# Sheet1-driver.net
KiCad netlist of a schematic drawn in Altium Designer
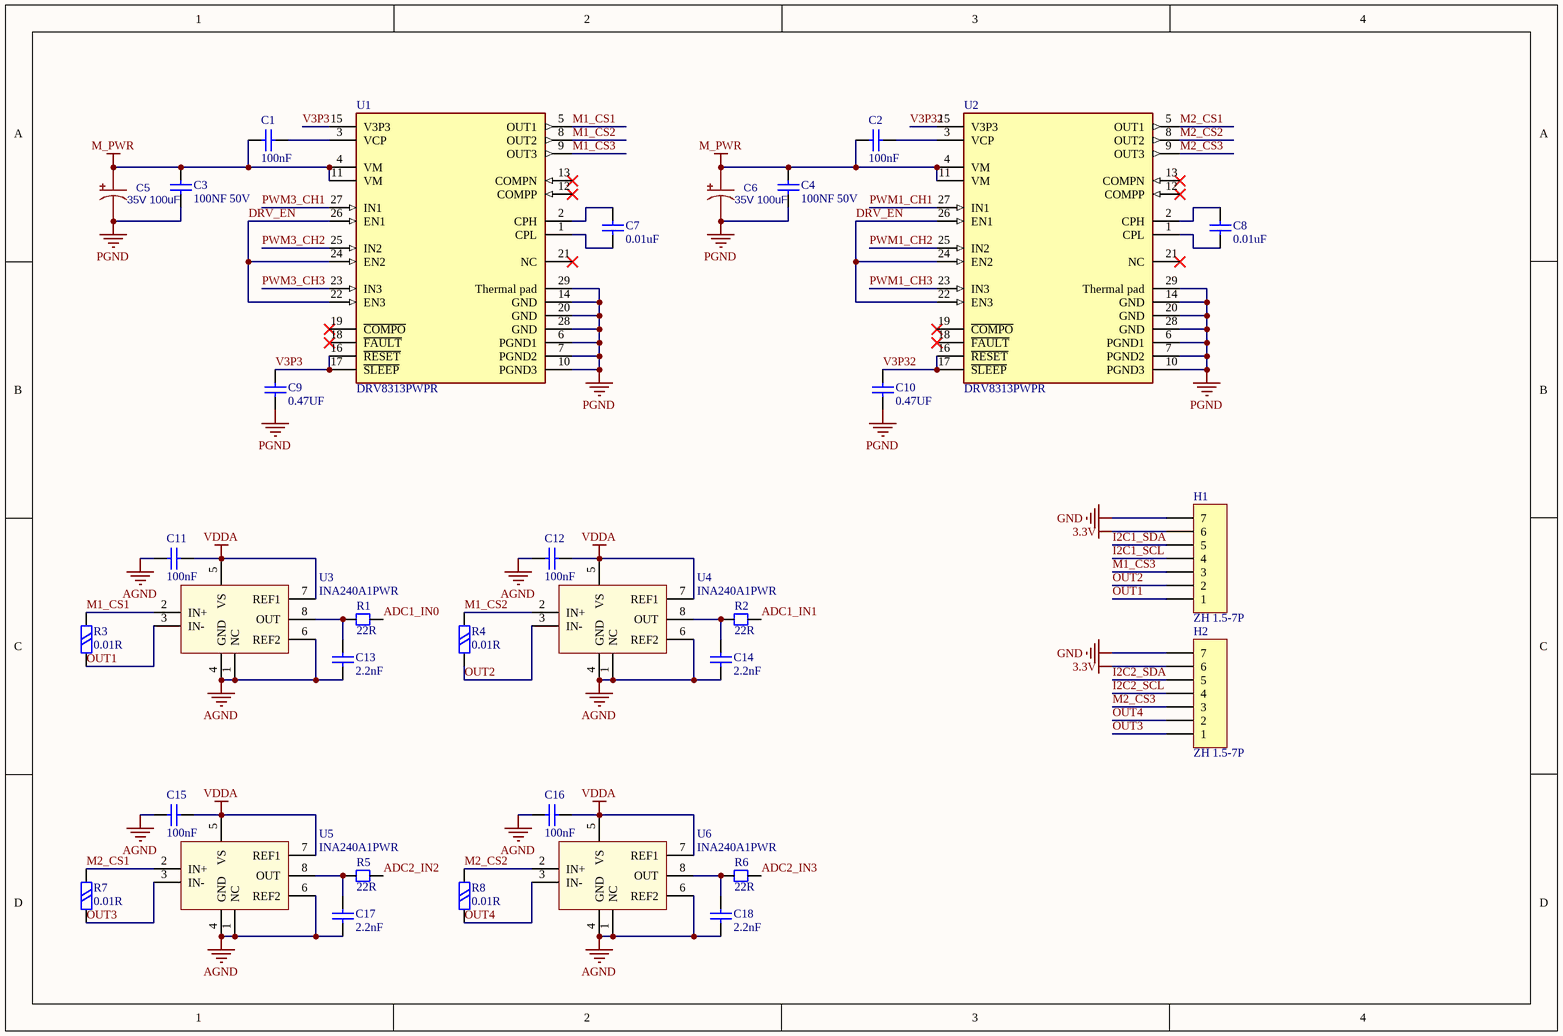
[diagram p0: Sheet1-driver.SchDoc]

(export (version "E")
  (design (tool "Eeschema 10.0.6"))
  (components
    (comp (ref "C1")
      (value "100nF")
      (footprint "CC1608-0603")
      (description "0603封装的电容")
      (fields (field (name "PUBLISHER") "Altium Limited"))
      (libsource (lib "base") (part "Cap Chip 0603"))
    )
    (comp (ref "C2")
      (value "100nF")
      (footprint "CC1608-0603")
      (description "0603封装的电容")
      (fields (field (name "PUBLISHER") "Altium Limited"))
      (libsource (lib "base") (part "Cap Chip 0603"))
    )
    (comp (ref "C3")
      (value "100NF 50V")
      (footprint "CC1608-0603")
      (description "0603封装的电容")
      (fields (field (name "PUBLISHER") "Altium Limited"))
      (libsource (lib "base") (part "Cap Chip 0603"))
    )
    (comp (ref "C4")
      (value "100NF 50V")
      (footprint "CC1608-0603")
      (description "0603封装的电容")
      (fields (field (name "PUBLISHER") "Altium Limited"))
      (libsource (lib "base") (part "Cap Chip 0603"))
    )
    (comp (ref "C5")
      (value "35V 100uF")
      (footprint "CAP-SMD_D6.3")
      (description "铝点解电容")
      (fields
        (field (name "BOM_SUPPLIER PART") "C413527")
        (field (name "BOM_MANUFACTURER PART") "EEEFP1C681AP")
        (field (name "CONTRIBUTOR") "LCSC")
      )
      (libsource (lib "base") (part "Cap ECAP SMD"))
    )
    (comp (ref "C6")
      (value "35V 100uF")
      (footprint "CAP-SMD_D6.3")
      (description "铝点解电容")
      (fields
        (field (name "BOM_SUPPLIER PART") "C413527")
        (field (name "BOM_MANUFACTURER PART") "EEEFP1C681AP")
        (field (name "CONTRIBUTOR") "LCSC")
      )
      (libsource (lib "base") (part "Cap ECAP SMD"))
    )
    (comp (ref "C7")
      (value "0.01uF")
      (footprint "CC1608-0603")
      (description "0603封装的电容")
      (fields (field (name "PUBLISHER") "Altium Limited"))
      (libsource (lib "base") (part "Cap Chip 0603"))
    )
    (comp (ref "C8")
      (value "0.01uF")
      (footprint "CC1608-0603")
      (description "0603封装的电容")
      (fields (field (name "PUBLISHER") "Altium Limited"))
      (libsource (lib "base") (part "Cap Chip 0603"))
    )
    (comp (ref "C9")
      (value "0.47UF")
      (footprint "CC1608-0603")
      (description "0603封装的电容")
      (fields (field (name "PUBLISHER") "Altium Limited"))
      (libsource (lib "base") (part "Cap Chip 0603"))
    )
    (comp (ref "C10")
      (value "0.47UF")
      (footprint "CC1608-0603")
      (description "0603封装的电容")
      (fields (field (name "PUBLISHER") "Altium Limited"))
      (libsource (lib "base") (part "Cap Chip 0603"))
    )
    (comp (ref "C11")
      (value "100nF")
      (footprint "CC1608-0603")
      (description "0603封装的电容")
      (fields (field (name "PUBLISHER") "Altium Limited"))
      (libsource (lib "base") (part "Cap Chip 0603"))
    )
    (comp (ref "C12")
      (value "100nF")
      (footprint "CC1608-0603")
      (description "0603封装的电容")
      (fields (field (name "PUBLISHER") "Altium Limited"))
      (libsource (lib "base") (part "Cap Chip 0603"))
    )
    (comp (ref "C13")
      (value "2.2nF")
      (footprint "CC1608-0603")
      (description "0603封装的电容")
      (fields (field (name "PUBLISHER") "Altium Limited"))
      (libsource (lib "base") (part "Cap Chip 0603"))
    )
    (comp (ref "C14")
      (value "2.2nF")
      (footprint "CC1608-0603")
      (description "0603封装的电容")
      (fields (field (name "PUBLISHER") "Altium Limited"))
      (libsource (lib "base") (part "Cap Chip 0603"))
    )
    (comp (ref "C15")
      (value "100nF")
      (footprint "CC1608-0603")
      (description "0603封装的电容")
      (fields (field (name "PUBLISHER") "Altium Limited"))
      (libsource (lib "base") (part "Cap Chip 0603"))
    )
    (comp (ref "C16")
      (value "100nF")
      (footprint "CC1608-0603")
      (description "0603封装的电容")
      (fields (field (name "PUBLISHER") "Altium Limited"))
      (libsource (lib "base") (part "Cap Chip 0603"))
    )
    (comp (ref "C17")
      (value "2.2nF")
      (footprint "CC1608-0603")
      (description "0603封装的电容")
      (fields (field (name "PUBLISHER") "Altium Limited"))
      (libsource (lib "base") (part "Cap Chip 0603"))
    )
    (comp (ref "C18")
      (value "2.2nF")
      (footprint "CC1608-0603")
      (description "0603封装的电容")
      (fields (field (name "PUBLISHER") "Altium Limited"))
      (libsource (lib "base") (part "Cap Chip 0603"))
    )
    (comp (ref "H1")
      (value "ZH 1.5-7P")
      (footprint "ZH1.5-7P")
      (description "ZH1.5-7P 间距1.5的贴片连接座")
      (libsource (lib "Connectors") (part "ZH 1.5-7P"))
    )
    (comp (ref "H2")
      (value "ZH 1.5-7P")
      (footprint "ZH1.5-7P")
      (description "ZH1.5-7P 间距1.5的贴片连接座")
      (libsource (lib "Connectors") (part "ZH 1.5-7P"))
    )
    (comp (ref "R1")
      (value "22R")
      (footprint "CR1608-0603")
      (description "0603封装电阻")
      (fields (field (name "PUBLISHER") "Altium Limited"))
      (libsource (lib "base") (part "Resistor Chip 0603"))
    )
    (comp (ref "R2")
      (value "22R")
      (footprint "CR1608-0603")
      (description "0603封装电阻")
      (fields (field (name "PUBLISHER") "Altium Limited"))
      (libsource (lib "base") (part "Resistor Chip 0603"))
    )
    (comp (ref "R3")
      (value "0.01R")
      (footprint "CR3216-1206")
      (description "1206封装电阻")
      (fields (field (name "PUBLISHER") "Altium Limited"))
      (libsource (lib "base") (part "Resistor Chip 1206"))
    )
    (comp (ref "R4")
      (value "0.01R")
      (footprint "CR3216-1206")
      (description "1206封装电阻")
      (fields (field (name "PUBLISHER") "Altium Limited"))
      (libsource (lib "base") (part "Resistor Chip 1206"))
    )
    (comp (ref "R5")
      (value "22R")
      (footprint "CR1608-0603")
      (description "0603封装电阻")
      (fields (field (name "PUBLISHER") "Altium Limited"))
      (libsource (lib "base") (part "Resistor Chip 0603"))
    )
    (comp (ref "R6")
      (value "22R")
      (footprint "CR1608-0603")
      (description "0603封装电阻")
      (fields (field (name "PUBLISHER") "Altium Limited"))
      (libsource (lib "base") (part "Resistor Chip 0603"))
    )
    (comp (ref "R7")
      (value "0.01R")
      (footprint "CR3216-1206")
      (description "1206封装电阻")
      (fields (field (name "PUBLISHER") "Altium Limited"))
      (libsource (lib "base") (part "Resistor Chip 1206"))
    )
    (comp (ref "R8")
      (value "0.01R")
      (footprint "CR3216-1206")
      (description "1206封装电阻")
      (fields (field (name "PUBLISHER") "Altium Limited"))
      (libsource (lib "base") (part "Resistor Chip 1206"))
    )
    (comp (ref "U1")
      (value "DRV8313PWPR")
      (footprint "HTSSOP-28")
      (description "独立控制的半 H 桥驱动器,主要用于驱动一个三项无刷电机IC MOTOR DRIVER 8V-60V 28HTSSOP")
      (libsource (lib "PB-Chip") (part "DRV8313"))
    )
    (comp (ref "U2")
      (value "DRV8313PWPR")
      (footprint "HTSSOP-28")
      (description "独立控制的半 H 桥驱动器,主要用于驱动一个三项无刷电机IC MOTOR DRIVER 8V-60V 28HTSSOP")
      (libsource (lib "PB-Chip") (part "DRV8313"))
    )
    (comp (ref "U3")
      (value "INA240A1PWR")
      (footprint "TSSOP-8")
      (description "超精密电流检测放大器")
      (libsource (lib "power-chip") (part "INA240A1PWR"))
    )
    (comp (ref "U4")
      (value "INA240A1PWR")
      (footprint "TSSOP-8")
      (description "超精密电流检测放大器")
      (libsource (lib "power-chip") (part "INA240A1PWR"))
    )
    (comp (ref "U5")
      (value "INA240A1PWR")
      (footprint "TSSOP-8")
      (description "超精密电流检测放大器")
      (libsource (lib "power-chip") (part "INA240A1PWR"))
    )
    (comp (ref "U6")
      (value "INA240A1PWR")
      (footprint "TSSOP-8")
      (description "超精密电流检测放大器")
      (libsource (lib "power-chip") (part "INA240A1PWR"))
    )
  )
  (nets
    (net (code "1") (name "/ADC1_IN0") (class "Default")
      (node (ref "R1") (pin "1") (pinfunction "1_1") (pintype "passive"))
    )
    (net (code "2") (name "/ADC1_IN1") (class "Default")
      (node (ref "R2") (pin "1") (pinfunction "1_1") (pintype "passive"))
    )
    (net (code "3") (name "/ADC2_IN2") (class "Default")
      (node (ref "R5") (pin "1") (pinfunction "1_1") (pintype "passive"))
    )
    (net (code "4") (name "/ADC2_IN3") (class "Default")
      (node (ref "R6") (pin "1") (pinfunction "1_1") (pintype "passive"))
    )
    (net (code "5") (name "/DRV_EN") (class "Default")
      (node (ref "U1") (pin "22") (pinfunction "EN3_22") (pintype "input"))
      (node (ref "U1") (pin "24") (pinfunction "EN2_24") (pintype "input"))
      (node (ref "U1") (pin "26") (pinfunction "EN1_26") (pintype "input"))
      (node (ref "U2") (pin "22") (pinfunction "EN3_22") (pintype "input"))
      (node (ref "U2") (pin "24") (pinfunction "EN2_24") (pintype "input"))
      (node (ref "U2") (pin "26") (pinfunction "EN1_26") (pintype "input"))
    )
    (net (code "6") (name "/I2C1_SCL") (class "Default")
      (node (ref "H1") (pin "4") (pinfunction "4_4") (pintype "passive"))
    )
    (net (code "7") (name "/I2C1_SDA") (class "Default")
      (node (ref "H1") (pin "5") (pinfunction "5_5") (pintype "passive"))
    )
    (net (code "8") (name "/I2C2_SCL") (class "Default")
      (node (ref "H2") (pin "4") (pinfunction "4_4") (pintype "passive"))
    )
    (net (code "9") (name "/I2C2_SDA") (class "Default")
      (node (ref "H2") (pin "5") (pinfunction "5_5") (pintype "passive"))
    )
    (net (code "10") (name "/M1_CS1") (class "Default")
      (node (ref "R3") (pin "2") (pinfunction "2_2") (pintype "passive"))
      (node (ref "U1") (pin "5") (pinfunction "OUT1_5") (pintype "output"))
      (node (ref "U3") (pin "2") (pinfunction "IN+_2") (pintype "passive"))
    )
    (net (code "11") (name "/M1_CS2") (class "Default")
      (node (ref "R4") (pin "2") (pinfunction "2_2") (pintype "passive"))
      (node (ref "U1") (pin "8") (pinfunction "OUT2_8") (pintype "output"))
      (node (ref "U4") (pin "2") (pinfunction "IN+_2") (pintype "passive"))
    )
    (net (code "12") (name "/M1_CS3") (class "Default")
      (node (ref "H1") (pin "3") (pinfunction "3_3") (pintype "passive"))
      (node (ref "U1") (pin "9") (pinfunction "OUT3_9") (pintype "output"))
    )
    (net (code "13") (name "/M2_CS1") (class "Default")
      (node (ref "R7") (pin "2") (pinfunction "2_2") (pintype "passive"))
      (node (ref "U2") (pin "5") (pinfunction "OUT1_5") (pintype "output"))
      (node (ref "U5") (pin "2") (pinfunction "IN+_2") (pintype "passive"))
    )
    (net (code "14") (name "/M2_CS2") (class "Default")
      (node (ref "R8") (pin "2") (pinfunction "2_2") (pintype "passive"))
      (node (ref "U2") (pin "8") (pinfunction "OUT2_8") (pintype "output"))
      (node (ref "U6") (pin "2") (pinfunction "IN+_2") (pintype "passive"))
    )
    (net (code "15") (name "/M2_CS3") (class "Default")
      (node (ref "H2") (pin "3") (pinfunction "3_3") (pintype "passive"))
      (node (ref "U2") (pin "9") (pinfunction "OUT3_9") (pintype "output"))
    )
    (net (code "16") (name "/OUT1") (class "Default")
      (node (ref "H1") (pin "1") (pinfunction "1_1") (pintype "passive"))
      (node (ref "R3") (pin "1") (pinfunction "1_1") (pintype "passive"))
      (node (ref "U3") (pin "3") (pinfunction "IN-_3") (pintype "passive"))
    )
    (net (code "17") (name "/OUT2") (class "Default")
      (node (ref "H1") (pin "2") (pinfunction "2_2") (pintype "passive"))
      (node (ref "R4") (pin "1") (pinfunction "1_1") (pintype "passive"))
      (node (ref "U4") (pin "3") (pinfunction "IN-_3") (pintype "passive"))
    )
    (net (code "18") (name "/OUT3") (class "Default")
      (node (ref "H2") (pin "1") (pinfunction "1_1") (pintype "passive"))
      (node (ref "R7") (pin "1") (pinfunction "1_1") (pintype "passive"))
      (node (ref "U5") (pin "3") (pinfunction "IN-_3") (pintype "passive"))
    )
    (net (code "19") (name "/OUT4") (class "Default")
      (node (ref "H2") (pin "2") (pinfunction "2_2") (pintype "passive"))
      (node (ref "R8") (pin "1") (pinfunction "1_1") (pintype "passive"))
      (node (ref "U6") (pin "3") (pinfunction "IN-_3") (pintype "passive"))
    )
    (net (code "20") (name "/PWM1_CH1") (class "Default")
      (node (ref "U2") (pin "27") (pinfunction "IN1_27") (pintype "input"))
    )
    (net (code "21") (name "/PWM1_CH2") (class "Default")
      (node (ref "U2") (pin "25") (pinfunction "IN2_25") (pintype "input"))
    )
    (net (code "22") (name "/PWM1_CH3") (class "Default")
      (node (ref "U2") (pin "23") (pinfunction "IN3_23") (pintype "input"))
    )
    (net (code "23") (name "/PWM3_CH1") (class "Default")
      (node (ref "U1") (pin "27") (pinfunction "IN1_27") (pintype "input"))
    )
    (net (code "24") (name "/PWM3_CH2") (class "Default")
      (node (ref "U1") (pin "25") (pinfunction "IN2_25") (pintype "input"))
    )
    (net (code "25") (name "/PWM3_CH3") (class "Default")
      (node (ref "U1") (pin "23") (pinfunction "IN3_23") (pintype "input"))
    )
    (net (code "26") (name "/V3P3") (class "Default")
      (node (ref "C9") (pin "1") (pinfunction "1_1") (pintype "passive"))
      (node (ref "U1") (pin "15") (pinfunction "V3P3_15") (pintype "power_in"))
      (node (ref "U1") (pin "16") (pinfunction "~{RESET}_16") (pintype "passive"))
      (node (ref "U1") (pin "17") (pinfunction "~{SLEEP}_17") (pintype "passive"))
    )
    (net (code "27") (name "/V3P32") (class "Default")
      (node (ref "C10") (pin "1") (pinfunction "1_1") (pintype "passive"))
      (node (ref "U2") (pin "15") (pinfunction "V3P3_15") (pintype "power_in"))
      (node (ref "U2") (pin "16") (pinfunction "~{RESET}_16") (pintype "passive"))
      (node (ref "U2") (pin "17") (pinfunction "~{SLEEP}_17") (pintype "passive"))
    )
    (net (code "28") (name "3.3V") (class "Default")
      (node (ref "H1") (pin "6") (pinfunction "6_6") (pintype "passive"))
      (node (ref "H2") (pin "6") (pinfunction "6_6") (pintype "passive"))
    )
    (net (code "29") (name "AGND") (class "Default")
      (node (ref "C11") (pin "2") (pinfunction "2_2") (pintype "passive"))
      (node (ref "C12") (pin "2") (pinfunction "2_2") (pintype "passive"))
      (node (ref "C13") (pin "1") (pinfunction "1_1") (pintype "passive"))
      (node (ref "C14") (pin "1") (pinfunction "1_1") (pintype "passive"))
      (node (ref "C15") (pin "2") (pinfunction "2_2") (pintype "passive"))
      (node (ref "C16") (pin "2") (pinfunction "2_2") (pintype "passive"))
      (node (ref "C17") (pin "1") (pinfunction "1_1") (pintype "passive"))
      (node (ref "C18") (pin "1") (pinfunction "1_1") (pintype "passive"))
      (node (ref "U3") (pin "1") (pinfunction "NC_1") (pintype "passive"))
      (node (ref "U3") (pin "4") (pinfunction "GND_4") (pintype "passive"))
      (node (ref "U3") (pin "6") (pinfunction "REF2_6") (pintype "passive"))
      (node (ref "U4") (pin "1") (pinfunction "NC_1") (pintype "passive"))
      (node (ref "U4") (pin "4") (pinfunction "GND_4") (pintype "passive"))
      (node (ref "U4") (pin "6") (pinfunction "REF2_6") (pintype "passive"))
      (node (ref "U5") (pin "1") (pinfunction "NC_1") (pintype "passive"))
      (node (ref "U5") (pin "4") (pinfunction "GND_4") (pintype "passive"))
      (node (ref "U5") (pin "6") (pinfunction "REF2_6") (pintype "passive"))
      (node (ref "U6") (pin "1") (pinfunction "NC_1") (pintype "passive"))
      (node (ref "U6") (pin "4") (pinfunction "GND_4") (pintype "passive"))
      (node (ref "U6") (pin "6") (pinfunction "REF2_6") (pintype "passive"))
    )
    (net (code "30") (name "GND") (class "Default")
      (node (ref "H1") (pin "7") (pinfunction "7_7") (pintype "passive"))
      (node (ref "H2") (pin "7") (pinfunction "7_7") (pintype "passive"))
    )
    (net (code "31") (name "M_PWR") (class "Default")
      (node (ref "C1") (pin "2") (pinfunction "2_2") (pintype "passive"))
      (node (ref "C2") (pin "2") (pinfunction "2_2") (pintype "passive"))
      (node (ref "C3") (pin "1") (pinfunction "1_1") (pintype "passive"))
      (node (ref "C4") (pin "1") (pinfunction "1_1") (pintype "passive"))
      (node (ref "C5") (pin "1") (pinfunction "1_1") (pintype "passive"))
      (node (ref "C6") (pin "1") (pinfunction "1_1") (pintype "passive"))
      (node (ref "U1") (pin "11") (pinfunction "VM_11") (pintype "power_in"))
      (node (ref "U1") (pin "4") (pinfunction "VM_4") (pintype "power_in"))
      (node (ref "U2") (pin "11") (pinfunction "VM_11") (pintype "power_in"))
      (node (ref "U2") (pin "4") (pinfunction "VM_4") (pintype "power_in"))
    )
    (net (code "32") (name "Net-(U1-CPH)") (class "Default")
      (node (ref "C7") (pin "1") (pinfunction "1_1") (pintype "passive"))
      (node (ref "U1") (pin "2") (pinfunction "CPH_2") (pintype "power_in"))
    )
    (net (code "33") (name "Net-(U1-CPL)") (class "Default")
      (node (ref "C7") (pin "2") (pinfunction "2_2") (pintype "passive"))
      (node (ref "U1") (pin "1") (pinfunction "CPL_1") (pintype "power_in"))
    )
    (net (code "34") (name "Net-(U1-VCP)") (class "Default")
      (node (ref "C1") (pin "1") (pinfunction "1_1") (pintype "passive"))
      (node (ref "U1") (pin "3") (pinfunction "VCP_3") (pintype "power_in"))
    )
    (net (code "35") (name "Net-(U2-CPH)") (class "Default")
      (node (ref "C8") (pin "1") (pinfunction "1_1") (pintype "passive"))
      (node (ref "U2") (pin "2") (pinfunction "CPH_2") (pintype "power_in"))
    )
    (net (code "36") (name "Net-(U2-CPL)") (class "Default")
      (node (ref "C8") (pin "2") (pinfunction "2_2") (pintype "passive"))
      (node (ref "U2") (pin "1") (pinfunction "CPL_1") (pintype "power_in"))
    )
    (net (code "37") (name "Net-(U2-VCP)") (class "Default")
      (node (ref "C2") (pin "1") (pinfunction "1_1") (pintype "passive"))
      (node (ref "U2") (pin "3") (pinfunction "VCP_3") (pintype "power_in"))
    )
    (net (code "38") (name "Net-(U3-OUT)") (class "Default")
      (node (ref "C13") (pin "2") (pinfunction "2_2") (pintype "passive"))
      (node (ref "R1") (pin "2") (pinfunction "2_2") (pintype "passive"))
      (node (ref "U3") (pin "8") (pinfunction "OUT_8") (pintype "passive"))
    )
    (net (code "39") (name "Net-(U4-OUT)") (class "Default")
      (node (ref "C14") (pin "2") (pinfunction "2_2") (pintype "passive"))
      (node (ref "R2") (pin "2") (pinfunction "2_2") (pintype "passive"))
      (node (ref "U4") (pin "8") (pinfunction "OUT_8") (pintype "passive"))
    )
    (net (code "40") (name "Net-(U5-OUT)") (class "Default")
      (node (ref "C17") (pin "2") (pinfunction "2_2") (pintype "passive"))
      (node (ref "R5") (pin "2") (pinfunction "2_2") (pintype "passive"))
      (node (ref "U5") (pin "8") (pinfunction "OUT_8") (pintype "passive"))
    )
    (net (code "41") (name "Net-(U6-OUT)") (class "Default")
      (node (ref "C18") (pin "2") (pinfunction "2_2") (pintype "passive"))
      (node (ref "R6") (pin "2") (pinfunction "2_2") (pintype "passive"))
      (node (ref "U6") (pin "8") (pinfunction "OUT_8") (pintype "passive"))
    )
    (net (code "42") (name "PGND") (class "Default")
      (node (ref "C10") (pin "2") (pinfunction "2_2") (pintype "passive"))
      (node (ref "C3") (pin "2") (pinfunction "2_2") (pintype "passive"))
      (node (ref "C4") (pin "2") (pinfunction "2_2") (pintype "passive"))
      (node (ref "C5") (pin "2") (pinfunction "2_2") (pintype "passive"))
      (node (ref "C6") (pin "2") (pinfunction "2_2") (pintype "passive"))
      (node (ref "C9") (pin "2") (pinfunction "2_2") (pintype "passive"))
      (node (ref "U1") (pin "10") (pinfunction "PGND3_10") (pintype "power_in"))
      (node (ref "U1") (pin "14") (pinfunction "GND_14") (pintype "power_in"))
      (node (ref "U1") (pin "20") (pinfunction "GND_20") (pintype "power_in"))
      (node (ref "U1") (pin "28") (pinfunction "GND_28") (pintype "power_in"))
      (node (ref "U1") (pin "29") (pinfunction "Thermal_pad_29") (pintype "power_in"))
      (node (ref "U1") (pin "6") (pinfunction "PGND1_6") (pintype "power_in"))
      (node (ref "U1") (pin "7") (pinfunction "PGND2_7") (pintype "power_in"))
      (node (ref "U2") (pin "10") (pinfunction "PGND3_10") (pintype "power_in"))
      (node (ref "U2") (pin "14") (pinfunction "GND_14") (pintype "power_in"))
      (node (ref "U2") (pin "20") (pinfunction "GND_20") (pintype "power_in"))
      (node (ref "U2") (pin "28") (pinfunction "GND_28") (pintype "power_in"))
      (node (ref "U2") (pin "29") (pinfunction "Thermal_pad_29") (pintype "power_in"))
      (node (ref "U2") (pin "6") (pinfunction "PGND1_6") (pintype "power_in"))
      (node (ref "U2") (pin "7") (pinfunction "PGND2_7") (pintype "power_in"))
    )
    (net (code "43") (name "VDDA") (class "Default")
      (node (ref "C11") (pin "1") (pinfunction "1_1") (pintype "passive"))
      (node (ref "C12") (pin "1") (pinfunction "1_1") (pintype "passive"))
      (node (ref "C15") (pin "1") (pinfunction "1_1") (pintype "passive"))
      (node (ref "C16") (pin "1") (pinfunction "1_1") (pintype "passive"))
      (node (ref "U3") (pin "5") (pinfunction "VS_5") (pintype "passive"))
      (node (ref "U3") (pin "7") (pinfunction "REF1_7") (pintype "passive"))
      (node (ref "U4") (pin "5") (pinfunction "VS_5") (pintype "passive"))
      (node (ref "U4") (pin "7") (pinfunction "REF1_7") (pintype "passive"))
      (node (ref "U5") (pin "5") (pinfunction "VS_5") (pintype "passive"))
      (node (ref "U5") (pin "7") (pinfunction "REF1_7") (pintype "passive"))
      (node (ref "U6") (pin "5") (pinfunction "VS_5") (pintype "passive"))
      (node (ref "U6") (pin "7") (pinfunction "REF1_7") (pintype "passive"))
    )
    (net (code "44") (name "unconnected-(U1-COMPN-Pad13)") (class "Default")
      (node (ref "U1") (pin "13") (pinfunction "COMPN_13") (pintype "input+no_connect"))
    )
    (net (code "45") (name "unconnected-(U1-COMPP-Pad12)") (class "Default")
      (node (ref "U1") (pin "12") (pinfunction "COMPP_12") (pintype "input+no_connect"))
    )
    (net (code "46") (name "unconnected-(U1-NC-Pad21)") (class "Default")
      (node (ref "U1") (pin "21") (pinfunction "NC_21") (pintype "passive+no_connect"))
    )
    (net (code "47") (name "unconnected-(U1-~{COMPO}-Pad19)") (class "Default")
      (node (ref "U1") (pin "19") (pinfunction "~{COMPO}_19") (pintype "open_collector+no_connect"))
    )
    (net (code "48") (name "unconnected-(U1-~{FAULT}-Pad18)") (class "Default")
      (node (ref "U1") (pin "18") (pinfunction "~{FAULT}_18") (pintype "open_collector+no_connect"))
    )
    (net (code "49") (name "unconnected-(U2-COMPN-Pad13)") (class "Default")
      (node (ref "U2") (pin "13") (pinfunction "COMPN_13") (pintype "input+no_connect"))
    )
    (net (code "50") (name "unconnected-(U2-COMPP-Pad12)") (class "Default")
      (node (ref "U2") (pin "12") (pinfunction "COMPP_12") (pintype "input+no_connect"))
    )
    (net (code "51") (name "unconnected-(U2-NC-Pad21)") (class "Default")
      (node (ref "U2") (pin "21") (pinfunction "NC_21") (pintype "passive+no_connect"))
    )
    (net (code "52") (name "unconnected-(U2-~{COMPO}-Pad19)") (class "Default")
      (node (ref "U2") (pin "19") (pinfunction "~{COMPO}_19") (pintype "open_collector+no_connect"))
    )
    (net (code "53") (name "unconnected-(U2-~{FAULT}-Pad18)") (class "Default")
      (node (ref "U2") (pin "18") (pinfunction "~{FAULT}_18") (pintype "open_collector+no_connect"))
    )
  )
)
